# SCH_SNES2NEO_2025-12-20.net
KiCad netlist of a schematic drawn in EasyEDA
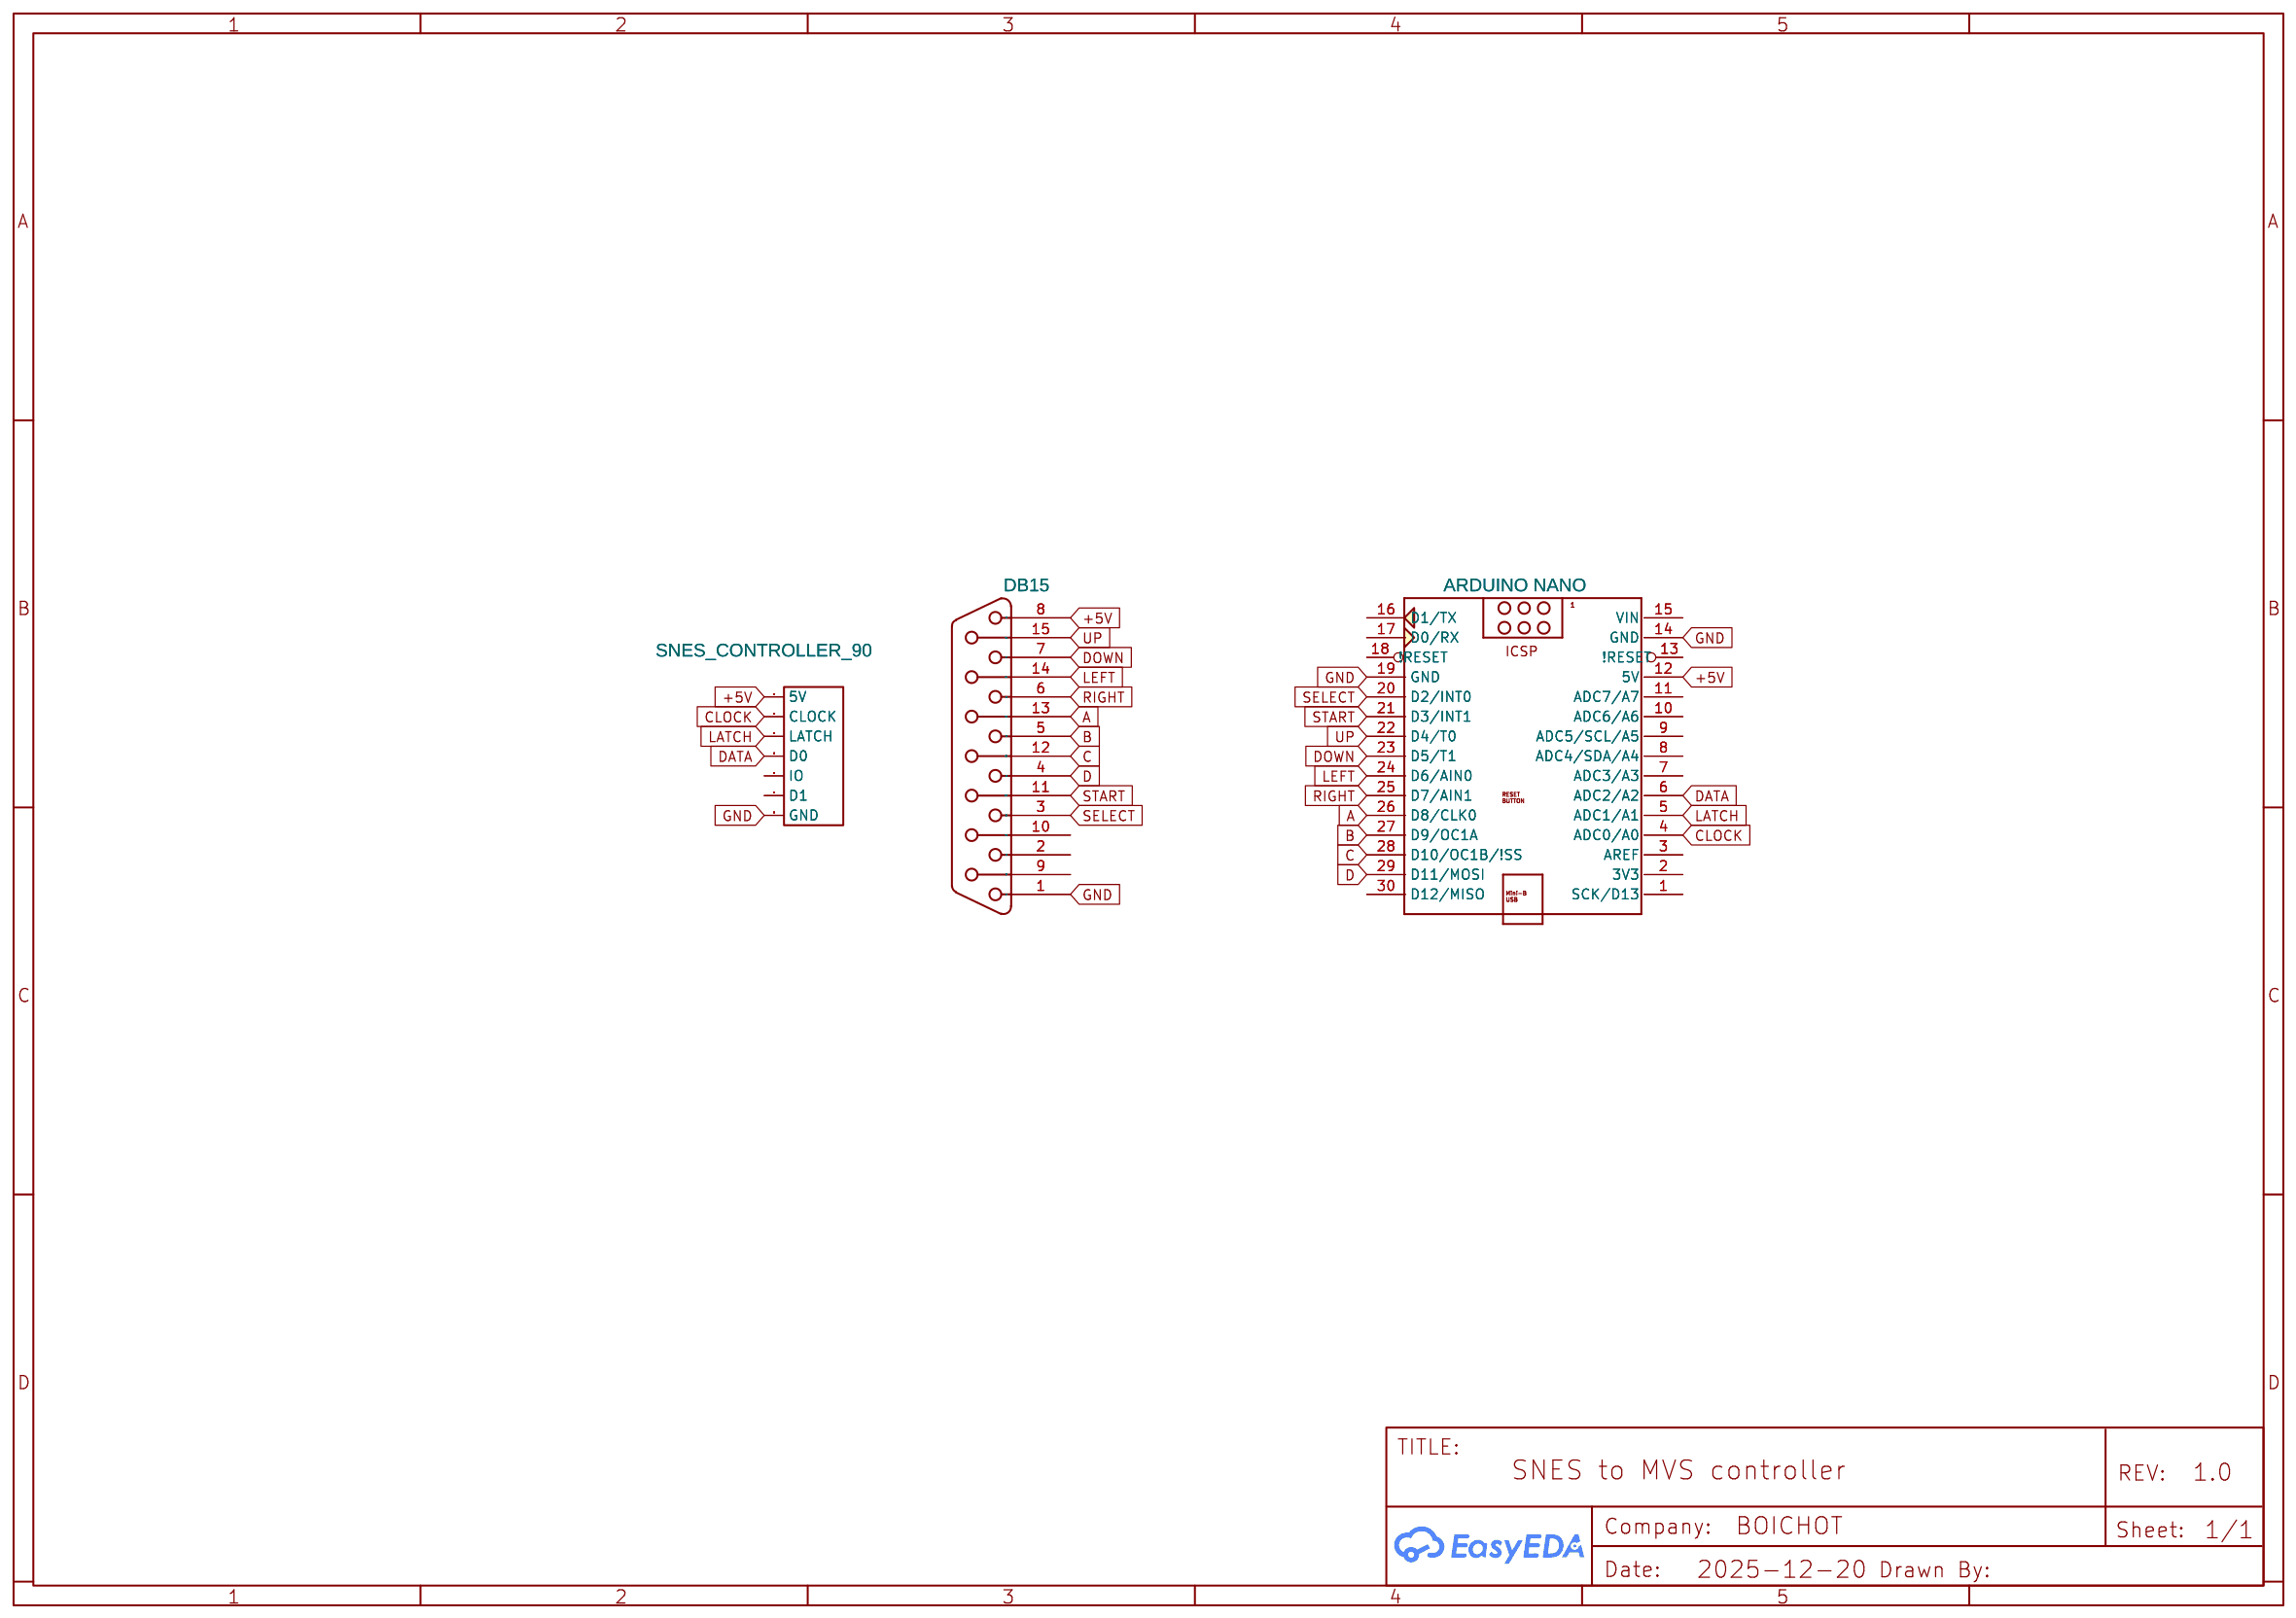
[diagram p0: schematic sheet]

(export (version "E")
  (design (tool "Eeschema 10.0.6"))
  (components
    (comp (ref "ARDUINO_NANO1") (value "ARDUINO NANO") (libsource (lib "") (part "ARDUINO NANO")))
    (comp (ref "H1") (value "SNES_CONTROLLER_90") (libsource (lib "") (part "SNES_CONTROLLER_90")))
    (comp (ref "J1") (value "DB15") (libsource (lib "") (part "DB15")))
  )
  (nets
    (net (code "1") (name "+5V") (class "Default")
      (node (ref "ARDUINO_NANO1") (pin "12") (pinfunction "5V_12") (pintype "bidirectional"))
      (node (ref "H1") (pin "5V") (pinfunction "5V_5V") (pintype "bidirectional"))
      (node (ref "J1") (pin "8") (pinfunction "8_8") (pintype "unspecified"))
    )
    (net (code "2") (name "A") (class "Default")
      (node (ref "ARDUINO_NANO1") (pin "26") (pinfunction "D8/CLK0_26") (pintype "bidirectional"))
      (node (ref "J1") (pin "13") (pinfunction "P13_13") (pintype "unspecified"))
    )
    (net (code "3") (name "B") (class "Default")
      (node (ref "ARDUINO_NANO1") (pin "27") (pinfunction "D9/OC1A_27") (pintype "bidirectional"))
      (node (ref "J1") (pin "5") (pinfunction "5_5") (pintype "unspecified"))
    )
    (net (code "4") (name "C") (class "Default")
      (node (ref "ARDUINO_NANO1") (pin "28") (pinfunction "D10/OC1B/!SS_28") (pintype "bidirectional"))
      (node (ref "J1") (pin "12") (pinfunction "P12_12") (pintype "unspecified"))
    )
    (net (code "5") (name "CLOCK") (class "Default")
      (node (ref "ARDUINO_NANO1") (pin "4") (pinfunction "ADC0/A0_4") (pintype "bidirectional"))
      (node (ref "H1") (pin "CLOCK") (pinfunction "CLOCK_CLOCK") (pintype "bidirectional"))
    )
    (net (code "6") (name "D") (class "Default")
      (node (ref "ARDUINO_NANO1") (pin "29") (pinfunction "D11/MOSI_29") (pintype "bidirectional"))
      (node (ref "J1") (pin "4") (pinfunction "4_4") (pintype "unspecified"))
    )
    (net (code "7") (name "DATA") (class "Default")
      (node (ref "ARDUINO_NANO1") (pin "6") (pinfunction "ADC2/A2_6") (pintype "bidirectional"))
      (node (ref "H1") (pin "D0") (pinfunction "D0_D0") (pintype "bidirectional"))
    )
    (net (code "8") (name "DOWN") (class "Default")
      (node (ref "ARDUINO_NANO1") (pin "23") (pinfunction "D5/T1_23") (pintype "bidirectional"))
      (node (ref "J1") (pin "7") (pinfunction "7_7") (pintype "unspecified"))
    )
    (net (code "9") (name "GND") (class "Default")
      (node (ref "ARDUINO_NANO1") (pin "14") (pinfunction "GND_14") (pintype "bidirectional"))
      (node (ref "ARDUINO_NANO1") (pin "19") (pinfunction "GND_19") (pintype "bidirectional"))
      (node (ref "H1") (pin "GND") (pinfunction "GND_GND") (pintype "bidirectional"))
      (node (ref "J1") (pin "1") (pinfunction "1_1") (pintype "unspecified"))
    )
    (net (code "10") (name "LATCH") (class "Default")
      (node (ref "ARDUINO_NANO1") (pin "5") (pinfunction "ADC1/A1_5") (pintype "bidirectional"))
      (node (ref "H1") (pin "LATCH") (pinfunction "LATCH_LATCH") (pintype "bidirectional"))
    )
    (net (code "11") (name "LEFT") (class "Default")
      (node (ref "ARDUINO_NANO1") (pin "24") (pinfunction "D6/AIN0_24") (pintype "bidirectional"))
      (node (ref "J1") (pin "14") (pinfunction "P14_14") (pintype "unspecified"))
    )
    (net (code "12") (name "RIGHT") (class "Default")
      (node (ref "ARDUINO_NANO1") (pin "25") (pinfunction "D7/AIN1_25") (pintype "bidirectional"))
      (node (ref "J1") (pin "6") (pinfunction "6_6") (pintype "unspecified"))
    )
    (net (code "13") (name "SELECT") (class "Default")
      (node (ref "ARDUINO_NANO1") (pin "20") (pinfunction "D2/INT0_20") (pintype "bidirectional"))
      (node (ref "J1") (pin "3") (pinfunction "3_3") (pintype "unspecified"))
    )
    (net (code "14") (name "START") (class "Default")
      (node (ref "ARDUINO_NANO1") (pin "21") (pinfunction "D3/INT1_21") (pintype "bidirectional"))
      (node (ref "J1") (pin "11") (pinfunction "P111_11") (pintype "unspecified"))
    )
    (net (code "15") (name "UP") (class "Default")
      (node (ref "ARDUINO_NANO1") (pin "22") (pinfunction "D4/T0_22") (pintype "bidirectional"))
      (node (ref "J1") (pin "15") (pinfunction "P15_15") (pintype "unspecified"))
    )
    (net (code "16") (name "unconnected-(ARDUINO_NANO1-!RESET-Pad13)") (class "Default")
      (node (ref "ARDUINO_NANO1") (pin "13") (pinfunction "!RESET_13") (pintype "bidirectional"))
    )
    (net (code "17") (name "unconnected-(ARDUINO_NANO1-!RESET-Pad18)") (class "Default")
      (node (ref "ARDUINO_NANO1") (pin "18") (pinfunction "!RESET_18") (pintype "bidirectional"))
    )
    (net (code "18") (name "unconnected-(ARDUINO_NANO1-3V3-Pad2)") (class "Default")
      (node (ref "ARDUINO_NANO1") (pin "2") (pinfunction "3V3_2") (pintype "bidirectional"))
    )
    (net (code "19") (name "unconnected-(ARDUINO_NANO1-ADC3{slash}A3-Pad7)") (class "Default")
      (node (ref "ARDUINO_NANO1") (pin "7") (pinfunction "ADC3/A3_7") (pintype "bidirectional"))
    )
    (net (code "20") (name "unconnected-(ARDUINO_NANO1-ADC4{slash}SDA{slash}A4-Pad8)") (class "Default")
      (node (ref "ARDUINO_NANO1") (pin "8") (pinfunction "ADC4/SDA/A4_8") (pintype "bidirectional"))
    )
    (net (code "21") (name "unconnected-(ARDUINO_NANO1-ADC5{slash}SCL{slash}A5-Pad9)") (class "Default")
      (node (ref "ARDUINO_NANO1") (pin "9") (pinfunction "ADC5/SCL/A5_9") (pintype "bidirectional"))
    )
    (net (code "22") (name "unconnected-(ARDUINO_NANO1-ADC6{slash}A6-Pad10)") (class "Default")
      (node (ref "ARDUINO_NANO1") (pin "10") (pinfunction "ADC6/A6_10") (pintype "bidirectional"))
    )
    (net (code "23") (name "unconnected-(ARDUINO_NANO1-ADC7{slash}A7-Pad11)") (class "Default")
      (node (ref "ARDUINO_NANO1") (pin "11") (pinfunction "ADC7/A7_11") (pintype "bidirectional"))
    )
    (net (code "24") (name "unconnected-(ARDUINO_NANO1-AREF-Pad3)") (class "Default")
      (node (ref "ARDUINO_NANO1") (pin "3") (pinfunction "AREF_3") (pintype "bidirectional"))
    )
    (net (code "25") (name "unconnected-(ARDUINO_NANO1-D0{slash}RX-Pad17)") (class "Default")
      (node (ref "ARDUINO_NANO1") (pin "17") (pinfunction "D0/RX_17") (pintype "bidirectional"))
    )
    (net (code "26") (name "unconnected-(ARDUINO_NANO1-D1{slash}TX-Pad16)") (class "Default")
      (node (ref "ARDUINO_NANO1") (pin "16") (pinfunction "D1/TX_16") (pintype "bidirectional"))
    )
    (net (code "27") (name "unconnected-(ARDUINO_NANO1-D12{slash}MISO-Pad30)") (class "Default")
      (node (ref "ARDUINO_NANO1") (pin "30") (pinfunction "D12/MISO_30") (pintype "bidirectional"))
    )
    (net (code "28") (name "unconnected-(ARDUINO_NANO1-SCK{slash}D13-Pad1)") (class "Default")
      (node (ref "ARDUINO_NANO1") (pin "1") (pinfunction "SCK/D13_1") (pintype "bidirectional"))
    )
    (net (code "29") (name "unconnected-(ARDUINO_NANO1-VIN-Pad15)") (class "Default")
      (node (ref "ARDUINO_NANO1") (pin "15") (pinfunction "VIN_15") (pintype "bidirectional"))
    )
    (net (code "30") (name "unconnected-(H1-PadD1)") (class "Default")
      (node (ref "H1") (pin "D1") (pinfunction "D1_D1") (pintype "bidirectional"))
    )
    (net (code "31") (name "unconnected-(H1-PadIO)") (class "Default")
      (node (ref "H1") (pin "IO") (pinfunction "IO_IO") (pintype "bidirectional"))
    )
    (net (code "32") (name "unconnected-(J1-P9-Pad9)") (class "Default")
      (node (ref "J1") (pin "9") (pinfunction "P9_9") (pintype "unspecified"))
    )
    (net (code "33") (name "unconnected-(J1-P10-Pad10)") (class "Default")
      (node (ref "J1") (pin "10") (pinfunction "P10_10") (pintype "unspecified"))
    )
    (net (code "34") (name "unconnected-(J1-Pad2)") (class "Default")
      (node (ref "J1") (pin "2") (pinfunction "2_2") (pintype "unspecified"))
    )
  )
)
